# Motor_4.net
KiCad netlist of a schematic drawn in Altium Designer
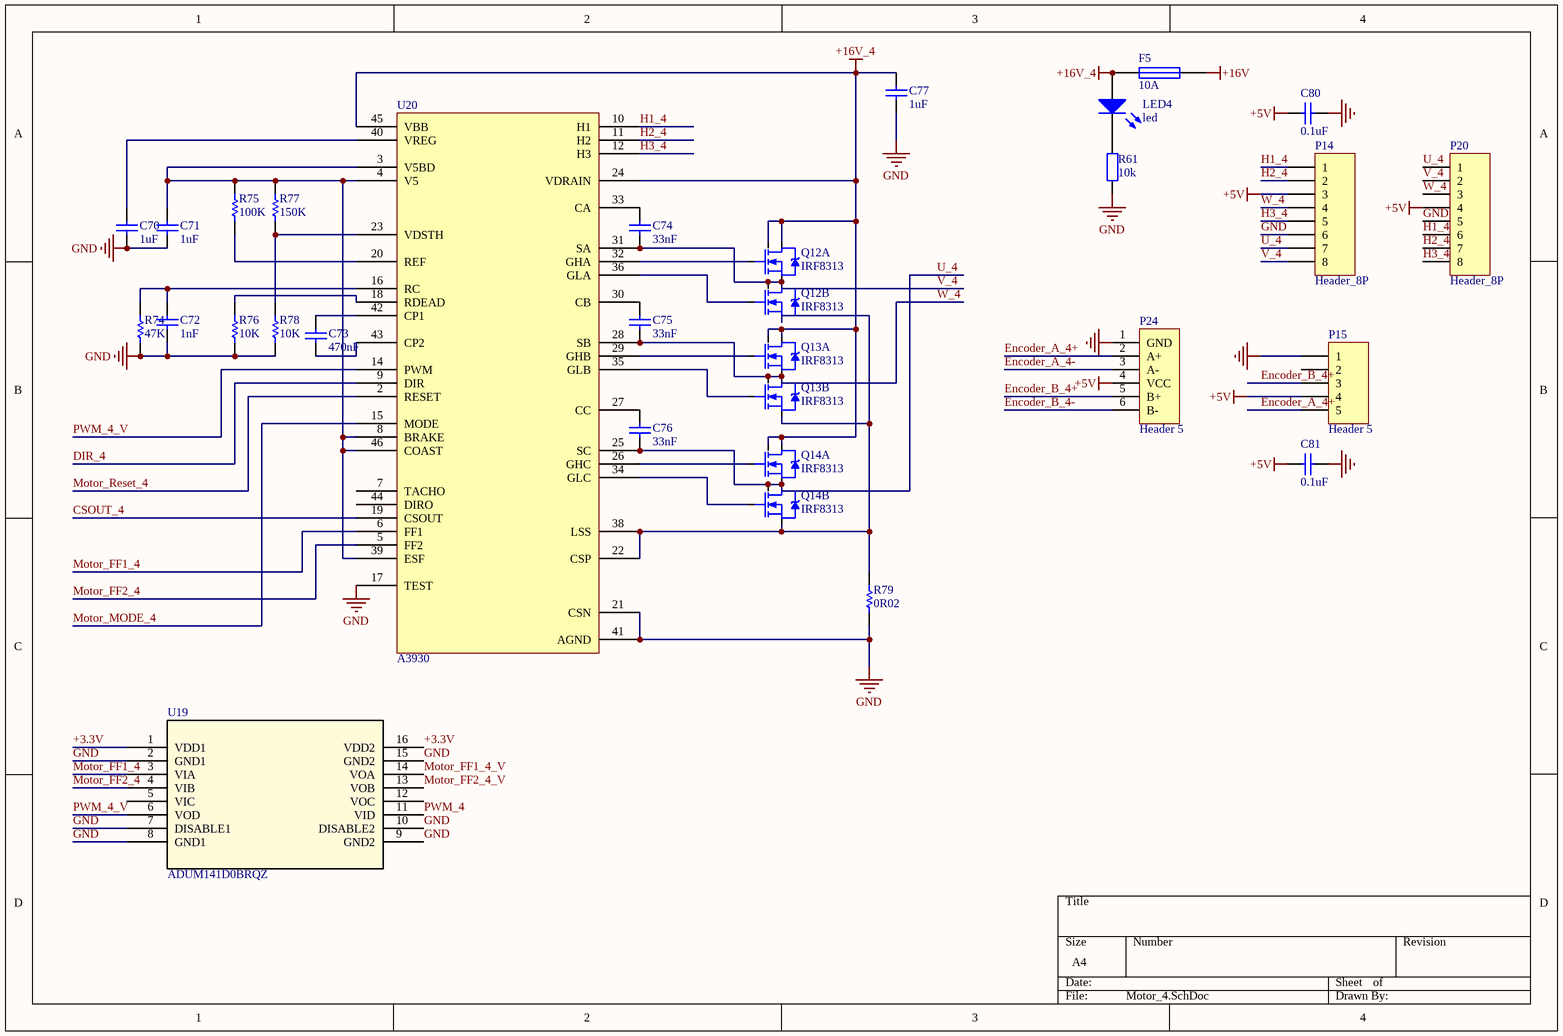
[diagram p0: Motor_4.SchDoc]

(export (version "E")
  (design (tool "Eeschema 10.0.6"))
  (components
    (comp (ref "C70")
      (value "1uF")
      (footprint "0603C")
      (description "Capacitor")
      (fields
        (field (name "MANUFACTURER") "Generic Components")
        (field (name "Comment") "1uf")
        (field (name "PUBLISHER") "Altium Hobart Technology Centre")
      )
      (libsource (lib "hp_2018_03") (part "Cap"))
    )
    (comp (ref "C71")
      (value "1uF")
      (footprint "0603C")
      (description "Capacitor")
      (fields
        (field (name "MANUFACTURER") "Generic Components")
        (field (name "Comment") "1uf")
        (field (name "PUBLISHER") "Altium Hobart Technology Centre")
      )
      (libsource (lib "hp_2018_03") (part "Cap"))
    )
    (comp (ref "C72")
      (value "1nF")
      (footprint "0603C")
      (description "Capacitor")
      (fields
        (field (name "MANUFACTURER") "Generic Components")
        (field (name "Comment") "1nf")
        (field (name "PUBLISHER") "Altium Hobart Technology Centre")
      )
      (libsource (lib "hp_2018_03") (part "Cap"))
    )
    (comp (ref "C73")
      (value "470nF")
      (footprint "0603C")
      (description "Capacitor")
      (fields
        (field (name "MANUFACTURER") "Generic Components")
        (field (name "Comment") "470nf")
        (field (name "PUBLISHER") "Altium Hobart Technology Centre")
      )
      (libsource (lib "hp_2018_03") (part "Cap"))
    )
    (comp (ref "C74")
      (value "33nF")
      (footprint "0603C")
      (description "Capacitor")
      (fields
        (field (name "MANUFACTURER") "Generic Components")
        (field (name "Comment") "33nf")
        (field (name "PUBLISHER") "Altium Hobart Technology Centre")
      )
      (libsource (lib "hp_2018_03") (part "Cap"))
    )
    (comp (ref "C75")
      (value "33nF")
      (footprint "0603C")
      (description "Capacitor")
      (fields
        (field (name "MANUFACTURER") "Generic Components")
        (field (name "Comment") "33nf")
        (field (name "PUBLISHER") "Altium Hobart Technology Centre")
      )
      (libsource (lib "hp_2018_03") (part "Cap"))
    )
    (comp (ref "C76")
      (value "33nF")
      (footprint "0603C")
      (description "Capacitor")
      (fields
        (field (name "MANUFACTURER") "Generic Components")
        (field (name "Comment") "33nf")
        (field (name "PUBLISHER") "Altium Hobart Technology Centre")
      )
      (libsource (lib "hp_2018_03") (part "Cap"))
    )
    (comp (ref "C77")
      (value "1uF")
      (footprint "0603C")
      (description "Capacitor")
      (fields
        (field (name "MANUFACTURER") "Generic Components")
        (field (name "Comment") "1uf")
        (field (name "PUBLISHER") "Altium Hobart Technology Centre")
      )
      (libsource (lib "hp_2018_03") (part "Cap"))
    )
    (comp (ref "C80")
      (value "0.1uF")
      (footprint "0603C")
      (description "Capacitor")
      (fields
        (field (name "MANUFACTURER") "Generic Components")
        (field (name "Comment") "0.1uf")
        (field (name "PUBLISHER") "Altium Hobart Technology Centre")
      )
      (libsource (lib "hp_2018_03") (part "Cap"))
    )
    (comp (ref "C81")
      (value "0.1uF")
      (footprint "0603C")
      (description "Capacitor")
      (fields
        (field (name "MANUFACTURER") "Generic Components")
        (field (name "Comment") "0.1uf")
        (field (name "PUBLISHER") "Altium Hobart Technology Centre")
      )
      (libsource (lib "hp_2018_03") (part "Cap"))
    )
    (comp (ref "F5")
      (value "10A")
      (footprint "Main_Board:FUSE_HEADER")
      (libsource (lib "Integrated_Library2") (part "FUSE"))
    )
    (comp (ref "LED4")
      (value "led")
      (footprint "0603_diode")
      (libsource (lib "Integrated_Library2") (part "led"))
    )
    (comp (ref "P14")
      (value "Header_8P")
      (footprint "8P - WF25122")
      (description "Used for Motor connection in ZJUNlict")
      (libsource (lib "Integrated_Library2") (part "Header_8P"))
    )
    (comp (ref "P15")
      (value "Header 5")
      (footprint "SHDR5")
      (description "Header, 5-Pin")
      (fields (field (name "PUBLISHER") "Altium Limited"))
      (libsource (lib "Miscellaneous Connectors") (part "Header 5"))
    )
    (comp (ref "P20")
      (value "Header_8P")
      (footprint "SHDR8")
      (description "Used for Motor connection in ZJUNlict")
      (libsource (lib "Integrated_Library2") (part "Header_8P"))
    )
    (comp (ref "P24")
      (value "Header 5")
      (footprint "SHDR6")
      (description "Header, 5-Pin")
      (fields (field (name "PUBLISHER") "Altium Limited"))
      (libsource (lib "Main_Board") (part "Header 6"))
    )
    (comp (ref "Q12") (value "IRF8313") (footprint "so-8 bg") (libsource (lib "BLDC") (part "SO-8 IRF8313")))
    (comp (ref "Q13") (value "IRF8313") (footprint "so-8 bg") (libsource (lib "BLDC") (part "SO-8 IRF8313")))
    (comp (ref "Q14") (value "IRF8313") (footprint "so-8 bg") (libsource (lib "BLDC") (part "SO-8 IRF8313")))
    (comp (ref "R61") (value "10k") (footprint "0603") (libsource (lib "Integrated_Library2") (part "res")))
    (comp (ref "R74")
      (value "47K")
      (footprint "0603R")
      (description "Resistor")
      (fields
        (field (name "MANUFACTURER") "Generic Components")
        (field (name "Comment") "47k")
        (field (name "PUBLISHER") "Altium Hobart Technology Centre")
      )
      (libsource (lib "hp_2018_03") (part "Res1"))
    )
    (comp (ref "R75")
      (value "100K")
      (footprint "0603R")
      (description "Resistor")
      (fields
        (field (name "MANUFACTURER") "Generic Components")
        (field (name "Comment") "100k")
        (field (name "PUBLISHER") "Altium Hobart Technology Centre")
      )
      (libsource (lib "hp_2018_03") (part "Res1"))
    )
    (comp (ref "R76")
      (value "10K")
      (footprint "0603R")
      (description "Resistor")
      (fields
        (field (name "MANUFACTURER") "Generic Components")
        (field (name "Comment") "10k")
        (field (name "PUBLISHER") "Altium Hobart Technology Centre")
      )
      (libsource (lib "hp_2018_03") (part "Res1"))
    )
    (comp (ref "R77")
      (value "150K")
      (footprint "0603R")
      (description "Resistor")
      (fields
        (field (name "MANUFACTURER") "Generic Components")
        (field (name "Comment") "150k")
        (field (name "PUBLISHER") "Altium Hobart Technology Centre")
      )
      (libsource (lib "hp_2018_03") (part "Res1"))
    )
    (comp (ref "R78")
      (value "10K")
      (footprint "0603R")
      (description "Resistor")
      (fields
        (field (name "MANUFACTURER") "Generic Components")
        (field (name "Comment") "10k")
        (field (name "PUBLISHER") "Altium Hobart Technology Centre")
      )
      (libsource (lib "hp_2018_03") (part "Res1"))
    )
    (comp (ref "R79")
      (value "0R02")
      (footprint "1206 10A")
      (description "Resistor")
      (fields
        (field (name "MANUFACTURER") "Generic Components")
        (field (name "Comment") "0.02")
        (field (name "PUBLISHER") "Altium Hobart Technology Centre")
      )
      (libsource (lib "hp_2018_03") (part "Res1"))
    )
    (comp (ref "U19")
      (value "ADUM141D0BRQZ")
      (footprint "Main_Board:RQ_16")
      (description "Imported")
      (libsource (lib "Main_Board") (part "ADUM141D0BRQZ"))
    )
    (comp (ref "U20") (value "A3930") (footprint "LQFP-48") (libsource (lib "BLDC") (part "LQFP 48")))
  )
  (nets
    (net (code "1") (name "+5V") (class "Default")
      (node (ref "C80") (pin "2") (pinfunction "2_2") (pintype "passive"))
      (node (ref "C81") (pin "2") (pinfunction "2_2") (pintype "passive"))
      (node (ref "P14") (pin "3") (pinfunction "3_3") (pintype "passive"))
      (node (ref "P15") (pin "4") (pinfunction "4_4") (pintype "passive"))
      (node (ref "P20") (pin "4") (pinfunction "4_4") (pintype "passive"))
      (node (ref "P24") (pin "4") (pinfunction "VCC_4") (pintype "passive"))
    )
    (net (code "2") (name "+16V") (class "Default")
      (node (ref "F5") (pin "1") (pinfunction "1_1") (pintype "passive"))
    )
    (net (code "3") (name "+16V_4") (class "Default")
      (node (ref "C77") (pin "2") (pinfunction "2_2") (pintype "passive"))
      (node (ref "F5") (pin "2") (pinfunction "2_2") (pintype "passive"))
      (node (ref "LED4") (pin "1") (pinfunction "A_1") (pintype "passive"))
      (node (ref "Q12") (pin "7") (pinfunction "D2_7") (pintype "passive"))
      (node (ref "Q12") (pin "8") (pinfunction "D2_8") (pintype "passive"))
      (node (ref "Q13") (pin "7") (pinfunction "D2_7") (pintype "passive"))
      (node (ref "Q13") (pin "8") (pinfunction "D2_8") (pintype "passive"))
      (node (ref "Q14") (pin "7") (pinfunction "D2_7") (pintype "passive"))
      (node (ref "Q14") (pin "8") (pinfunction "D2_8") (pintype "passive"))
      (node (ref "U20") (pin "24") (pinfunction "VDRAIN_24") (pintype "passive"))
      (node (ref "U20") (pin "45") (pinfunction "VBB_45") (pintype "passive"))
    )
    (net (code "4") (name "/+3.3V") (class "Default")
      (node (ref "U19") (pin "1") (pinfunction "VDD1_1") (pintype "passive"))
      (node (ref "U19") (pin "16") (pinfunction "VDD2_16") (pintype "passive"))
    )
    (net (code "5") (name "/CSOUT_4") (class "Default")
      (node (ref "U20") (pin "19") (pinfunction "CSOUT_19") (pintype "passive"))
    )
    (net (code "6") (name "/DIR_4") (class "Default")
      (node (ref "U20") (pin "9") (pinfunction "DIR_9") (pintype "passive"))
    )
    (net (code "7") (name "/Encoder_A_4+") (class "Default")
      (node (ref "P15") (pin "5") (pinfunction "5_5") (pintype "passive"))
      (node (ref "P24") (pin "2") (pinfunction "A+_2") (pintype "passive"))
    )
    (net (code "8") (name "/Encoder_A_4-") (class "Default")
      (node (ref "P24") (pin "3") (pinfunction "A-_3") (pintype "passive"))
    )
    (net (code "9") (name "/Encoder_B_4+") (class "Default")
      (node (ref "P15") (pin "3") (pinfunction "3_3") (pintype "passive"))
      (node (ref "P24") (pin "5") (pinfunction "B+_5") (pintype "passive"))
    )
    (net (code "10") (name "/Encoder_B_4-") (class "Default")
      (node (ref "P24") (pin "6") (pinfunction "B-_6") (pintype "passive"))
    )
    (net (code "11") (name "/H1_4") (class "Default")
      (node (ref "P14") (pin "1") (pinfunction "1_1") (pintype "passive"))
      (node (ref "P20") (pin "6") (pinfunction "6_6") (pintype "passive"))
      (node (ref "U20") (pin "10") (pinfunction "H1_10") (pintype "passive"))
    )
    (net (code "12") (name "/H2_4") (class "Default")
      (node (ref "P14") (pin "2") (pinfunction "2_2") (pintype "passive"))
      (node (ref "P20") (pin "7") (pinfunction "7_7") (pintype "passive"))
      (node (ref "U20") (pin "11") (pinfunction "H2_11") (pintype "passive"))
    )
    (net (code "13") (name "/H3_4") (class "Default")
      (node (ref "P14") (pin "5") (pinfunction "5_5") (pintype "passive"))
      (node (ref "P20") (pin "8") (pinfunction "8_8") (pintype "passive"))
      (node (ref "U20") (pin "12") (pinfunction "H3_12") (pintype "passive"))
    )
    (net (code "14") (name "/Motor_FF1_4") (class "Default")
      (node (ref "U19") (pin "3") (pinfunction "VIA_3") (pintype "passive"))
      (node (ref "U20") (pin "6") (pinfunction "FF1_6") (pintype "passive"))
    )
    (net (code "15") (name "/Motor_FF1_4_V") (class "Default")
      (node (ref "U19") (pin "14") (pinfunction "VOA_14") (pintype "passive"))
    )
    (net (code "16") (name "/Motor_FF2_4") (class "Default")
      (node (ref "U19") (pin "4") (pinfunction "VIB_4") (pintype "passive"))
      (node (ref "U20") (pin "5") (pinfunction "FF2_5") (pintype "passive"))
    )
    (net (code "17") (name "/Motor_FF2_4_V") (class "Default")
      (node (ref "U19") (pin "13") (pinfunction "VOB_13") (pintype "passive"))
    )
    (net (code "18") (name "/Motor_MODE_4") (class "Default")
      (node (ref "U20") (pin "15") (pinfunction "MODE_15") (pintype "passive"))
    )
    (net (code "19") (name "/Motor_Reset_4") (class "Default")
      (node (ref "U20") (pin "2") (pinfunction "RESET_2") (pintype "passive"))
    )
    (net (code "20") (name "/PWM_4") (class "Default")
      (node (ref "U19") (pin "11") (pinfunction "VID_11") (pintype "passive"))
    )
    (net (code "21") (name "/PWM_4_V") (class "Default")
      (node (ref "U19") (pin "6") (pinfunction "VOD_6") (pintype "passive"))
      (node (ref "U20") (pin "14") (pinfunction "PWM_14") (pintype "passive"))
    )
    (net (code "22") (name "/U_4") (class "Default")
      (node (ref "C76") (pin "1") (pinfunction "1_1") (pintype "passive"))
      (node (ref "P14") (pin "7") (pinfunction "7_7") (pintype "passive"))
      (node (ref "P20") (pin "1") (pinfunction "1_1") (pintype "passive"))
      (node (ref "Q14") (pin "1") (pinfunction "S2_1") (pintype "passive"))
      (node (ref "Q14") (pin "5") (pinfunction "D1_5") (pintype "passive"))
      (node (ref "Q14") (pin "6") (pinfunction "D1_6") (pintype "passive"))
      (node (ref "U20") (pin "25") (pinfunction "SC_25") (pintype "passive"))
    )
    (net (code "23") (name "/V_4") (class "Default")
      (node (ref "C74") (pin "1") (pinfunction "1_1") (pintype "passive"))
      (node (ref "P14") (pin "8") (pinfunction "8_8") (pintype "passive"))
      (node (ref "P20") (pin "2") (pinfunction "2_2") (pintype "passive"))
      (node (ref "Q12") (pin "1") (pinfunction "S2_1") (pintype "passive"))
      (node (ref "Q12") (pin "5") (pinfunction "D1_5") (pintype "passive"))
      (node (ref "Q12") (pin "6") (pinfunction "D1_6") (pintype "passive"))
      (node (ref "U20") (pin "31") (pinfunction "SA_31") (pintype "passive"))
    )
    (net (code "24") (name "/W_4") (class "Default")
      (node (ref "C75") (pin "1") (pinfunction "1_1") (pintype "passive"))
      (node (ref "P14") (pin "4") (pinfunction "4_4") (pintype "passive"))
      (node (ref "P20") (pin "3") (pinfunction "3_3") (pintype "passive"))
      (node (ref "Q13") (pin "1") (pinfunction "S2_1") (pintype "passive"))
      (node (ref "Q13") (pin "5") (pinfunction "D1_5") (pintype "passive"))
      (node (ref "Q13") (pin "6") (pinfunction "D1_6") (pintype "passive"))
      (node (ref "U20") (pin "28") (pinfunction "SB_28") (pintype "passive"))
    )
    (net (code "25") (name "GND") (class "Default")
      (node (ref "C70") (pin "1") (pinfunction "1_1") (pintype "passive"))
      (node (ref "C71") (pin "1") (pinfunction "1_1") (pintype "passive"))
      (node (ref "C72") (pin "1") (pinfunction "1_1") (pintype "passive"))
      (node (ref "C77") (pin "1") (pinfunction "1_1") (pintype "passive"))
      (node (ref "C80") (pin "1") (pinfunction "1_1") (pintype "passive"))
      (node (ref "C81") (pin "1") (pinfunction "1_1") (pintype "passive"))
      (node (ref "P14") (pin "6") (pinfunction "6_6") (pintype "passive"))
      (node (ref "P15") (pin "1") (pinfunction "1_1") (pintype "passive"))
      (node (ref "P20") (pin "5") (pinfunction "5_5") (pintype "passive"))
      (node (ref "P24") (pin "1") (pinfunction "GND_1") (pintype "passive"))
      (node (ref "R61") (pin "1") (pinfunction "1_1") (pintype "passive"))
      (node (ref "R74") (pin "1") (pinfunction "1_1") (pintype "passive"))
      (node (ref "R76") (pin "1") (pinfunction "1_1") (pintype "passive"))
      (node (ref "R78") (pin "1") (pinfunction "1_1") (pintype "passive"))
      (node (ref "R79") (pin "1") (pinfunction "1_1") (pintype "passive"))
      (node (ref "U19") (pin "10") (pinfunction "DISABLE2_10") (pintype "passive"))
      (node (ref "U19") (pin "15") (pinfunction "GND2_15") (pintype "passive"))
      (node (ref "U19") (pin "2") (pinfunction "GND1_2") (pintype "passive"))
      (node (ref "U19") (pin "7") (pinfunction "DISABLE1_7") (pintype "passive"))
      (node (ref "U19") (pin "8") (pinfunction "GND1_8") (pintype "passive"))
      (node (ref "U19") (pin "9") (pinfunction "GND2_9") (pintype "passive"))
      (node (ref "U20") (pin "17") (pinfunction "TEST_17") (pintype "passive"))
      (node (ref "U20") (pin "21") (pinfunction "CSN_21") (pintype "passive"))
      (node (ref "U20") (pin "41") (pinfunction "AGND_41") (pintype "passive"))
    )
    (net (code "26") (name "Net-(LED4-K)") (class "Default")
      (node (ref "LED4") (pin "2") (pinfunction "K_2") (pintype "passive"))
      (node (ref "R61") (pin "2") (pinfunction "2_2") (pintype "passive"))
    )
    (net (code "27") (name "Net-(Q12A-G2)") (class "Default")
      (node (ref "Q12") (pin "2") (pinfunction "G2_2") (pintype "passive"))
      (node (ref "U20") (pin "32") (pinfunction "GHA_32") (pintype "passive"))
    )
    (net (code "28") (name "Net-(Q12B-G1)") (class "Default")
      (node (ref "Q12") (pin "4") (pinfunction "G1_4") (pintype "passive"))
      (node (ref "U20") (pin "36") (pinfunction "GLA_36") (pintype "passive"))
    )
    (net (code "29") (name "Net-(Q12B-S1)") (class "Default")
      (node (ref "Q12") (pin "3") (pinfunction "S1_3") (pintype "passive"))
      (node (ref "Q13") (pin "3") (pinfunction "S1_3") (pintype "passive"))
      (node (ref "Q14") (pin "3") (pinfunction "S1_3") (pintype "passive"))
      (node (ref "R79") (pin "2") (pinfunction "2_2") (pintype "passive"))
      (node (ref "U20") (pin "22") (pinfunction "CSP_22") (pintype "passive"))
      (node (ref "U20") (pin "38") (pinfunction "LSS_38") (pintype "passive"))
    )
    (net (code "30") (name "Net-(Q13A-G2)") (class "Default")
      (node (ref "Q13") (pin "2") (pinfunction "G2_2") (pintype "passive"))
      (node (ref "U20") (pin "29") (pinfunction "GHB_29") (pintype "passive"))
    )
    (net (code "31") (name "Net-(Q13B-G1)") (class "Default")
      (node (ref "Q13") (pin "4") (pinfunction "G1_4") (pintype "passive"))
      (node (ref "U20") (pin "35") (pinfunction "GLB_35") (pintype "passive"))
    )
    (net (code "32") (name "Net-(Q14A-G2)") (class "Default")
      (node (ref "Q14") (pin "2") (pinfunction "G2_2") (pintype "passive"))
      (node (ref "U20") (pin "26") (pinfunction "GHC_26") (pintype "passive"))
    )
    (net (code "33") (name "Net-(Q14B-G1)") (class "Default")
      (node (ref "Q14") (pin "4") (pinfunction "G1_4") (pintype "passive"))
      (node (ref "U20") (pin "34") (pinfunction "GLC_34") (pintype "passive"))
    )
    (net (code "34") (name "Net-(U20-BRAKE)") (class "Default")
      (node (ref "C71") (pin "2") (pinfunction "2_2") (pintype "passive"))
      (node (ref "R75") (pin "2") (pinfunction "2_2") (pintype "passive"))
      (node (ref "R77") (pin "2") (pinfunction "2_2") (pintype "passive"))
      (node (ref "U20") (pin "3") (pinfunction "V5BD_3") (pintype "passive"))
      (node (ref "U20") (pin "39") (pinfunction "ESF_39") (pintype "passive"))
      (node (ref "U20") (pin "4") (pinfunction "V5_4") (pintype "passive"))
      (node (ref "U20") (pin "46") (pinfunction "COAST_46") (pintype "passive"))
      (node (ref "U20") (pin "8") (pinfunction "BRAKE_8") (pintype "passive"))
    )
    (net (code "35") (name "Net-(U20-CA)") (class "Default")
      (node (ref "C74") (pin "2") (pinfunction "2_2") (pintype "passive"))
      (node (ref "U20") (pin "33") (pinfunction "CA_33") (pintype "passive"))
    )
    (net (code "36") (name "Net-(U20-CB)") (class "Default")
      (node (ref "C75") (pin "2") (pinfunction "2_2") (pintype "passive"))
      (node (ref "U20") (pin "30") (pinfunction "CB_30") (pintype "passive"))
    )
    (net (code "37") (name "Net-(U20-CC)") (class "Default")
      (node (ref "C76") (pin "2") (pinfunction "2_2") (pintype "passive"))
      (node (ref "U20") (pin "27") (pinfunction "CC_27") (pintype "passive"))
    )
    (net (code "38") (name "Net-(U20-CP1)") (class "Default")
      (node (ref "C73") (pin "2") (pinfunction "2_2") (pintype "passive"))
      (node (ref "U20") (pin "42") (pinfunction "CP1_42") (pintype "passive"))
    )
    (net (code "39") (name "Net-(U20-CP2)") (class "Default")
      (node (ref "C73") (pin "1") (pinfunction "1_1") (pintype "passive"))
      (node (ref "U20") (pin "43") (pinfunction "CP2_43") (pintype "passive"))
    )
    (net (code "40") (name "Net-(U20-RC)") (class "Default")
      (node (ref "C72") (pin "2") (pinfunction "2_2") (pintype "passive"))
      (node (ref "R74") (pin "2") (pinfunction "2_2") (pintype "passive"))
      (node (ref "U20") (pin "16") (pinfunction "RC_16") (pintype "passive"))
    )
    (net (code "41") (name "Net-(U20-RDEAD)") (class "Default")
      (node (ref "R76") (pin "2") (pinfunction "2_2") (pintype "passive"))
      (node (ref "U20") (pin "18") (pinfunction "RDEAD_18") (pintype "passive"))
    )
    (net (code "42") (name "Net-(U20-REF)") (class "Default")
      (node (ref "R75") (pin "1") (pinfunction "1_1") (pintype "passive"))
      (node (ref "U20") (pin "20") (pinfunction "REF_20") (pintype "passive"))
    )
    (net (code "43") (name "Net-(U20-VDSTH)") (class "Default")
      (node (ref "R77") (pin "1") (pinfunction "1_1") (pintype "passive"))
      (node (ref "R78") (pin "2") (pinfunction "2_2") (pintype "passive"))
      (node (ref "U20") (pin "23") (pinfunction "VDSTH_23") (pintype "passive"))
    )
    (net (code "44") (name "Net-(U20-VREG)") (class "Default")
      (node (ref "C70") (pin "2") (pinfunction "2_2") (pintype "passive"))
      (node (ref "U20") (pin "40") (pinfunction "VREG_40") (pintype "passive"))
    )
    (net (code "45") (name "unconnected-(P15-Pad2)") (class "Default")
      (node (ref "P15") (pin "2") (pinfunction "2_2") (pintype "passive"))
    )
    (net (code "46") (name "unconnected-(U19-VIC-Pad5)") (class "Default")
      (node (ref "U19") (pin "5") (pinfunction "VIC_5") (pintype "passive"))
    )
    (net (code "47") (name "unconnected-(U19-VOC-Pad12)") (class "Default")
      (node (ref "U19") (pin "12") (pinfunction "VOC_12") (pintype "passive"))
    )
    (net (code "48") (name "unconnected-(U20-DIRO-Pad44)") (class "Default")
      (node (ref "U20") (pin "44") (pinfunction "DIRO_44") (pintype "passive"))
    )
    (net (code "49") (name "unconnected-(U20-TACHO-Pad7)") (class "Default")
      (node (ref "U20") (pin "7") (pinfunction "TACHO_7") (pintype "passive"))
    )
  )
)
